# ADC.net
KiCad netlist of a schematic drawn in Altium Designer
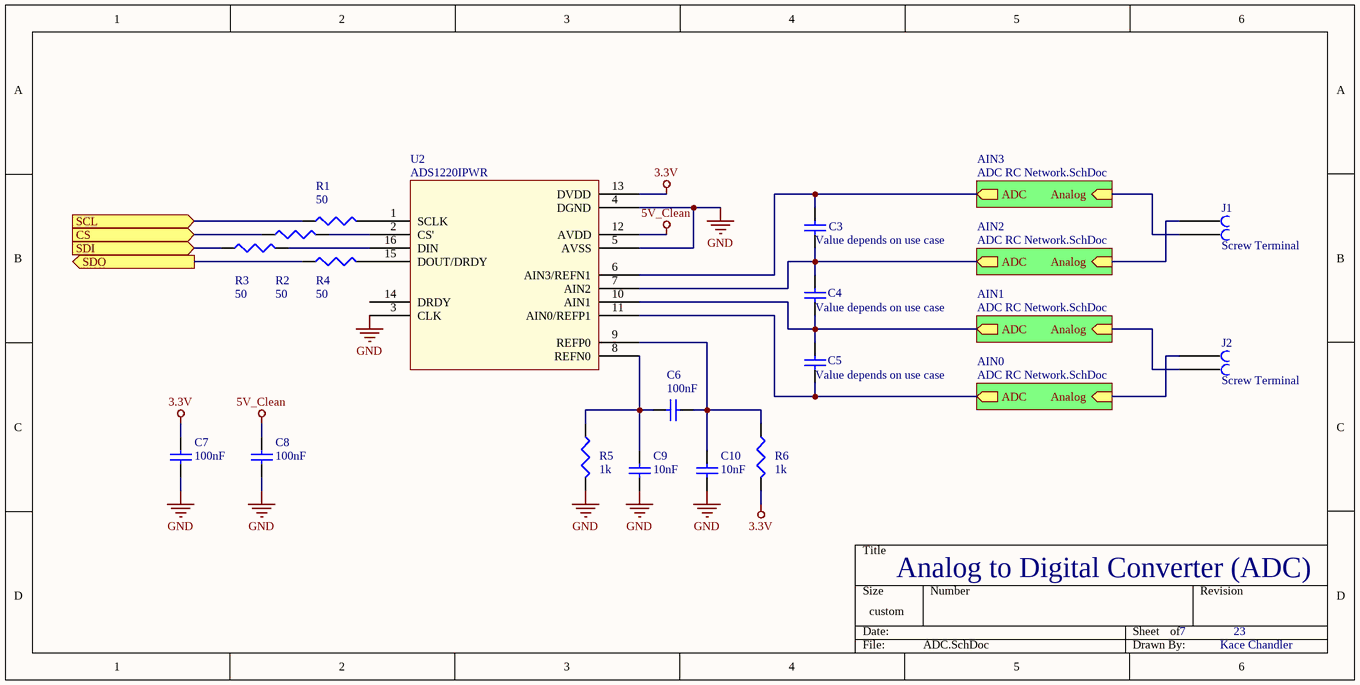
[diagram p0: ADC.SchDoc]

(export (version "E")
  (design (tool "Eeschema 10.0.6"))
  (components
    (comp (ref "C3")
      (value "Value depends on use case")
      (footprint "0603 to 0805 SMD")
      (description "Capacitor")
      (fields (field (name "Comment") "Cap") (field (name "PUBLISHER") "Altium Limited"))
      (libsource (lib "Miscellaneous Devices") (part "Cap"))
    )
    (comp (ref "C4")
      (value "Value depends on use case")
      (footprint "0603 to 0805 SMD")
      (description "Capacitor")
      (fields (field (name "Comment") "Cap") (field (name "PUBLISHER") "Altium Limited"))
      (libsource (lib "Miscellaneous Devices") (part "Cap"))
    )
    (comp (ref "C5")
      (value "Value depends on use case")
      (footprint "0603 to 0805 SMD")
      (description "Capacitor")
      (fields (field (name "Comment") "Cap") (field (name "PUBLISHER") "Altium Limited"))
      (libsource (lib "Miscellaneous Devices") (part "Cap"))
    )
    (comp (ref "C6")
      (value "100nF")
      (footprint "0603 to 0805 SMD")
      (fields (field (name "Comment") "Cap"))
      (libsource (lib "RC0805FR-0751K1L") (part "Cap"))
    )
    (comp (ref "C7")
      (value "100nF")
      (footprint "0603 Footprint")
      (fields (field (name "Comment") "Cap"))
      (libsource (lib "RC0805FR-0751K1L") (part "Cap"))
    )
    (comp (ref "C8")
      (value "100nF")
      (footprint "0603 Footprint")
      (fields (field (name "Comment") "Cap"))
      (libsource (lib "RC0805FR-0751K1L") (part "Cap"))
    )
    (comp (ref "C9")
      (value "10nF")
      (footprint "0603 to 0805 SMD")
      (fields (field (name "Comment") "Cap"))
      (libsource (lib "RC0805FR-0751K1L") (part "Cap"))
    )
    (comp (ref "C10")
      (value "10nF")
      (footprint "0603 to 0805 SMD")
      (fields (field (name "Comment") "Cap"))
      (libsource (lib "RC0805FR-0751K1L") (part "Cap"))
    )
    (comp (ref "J1")
      (value "Screw Terminal")
      (footprint "Screw Terminal")
      (libsource (lib "AvionicsParts") (part "Screw Terminal"))
    )
    (comp (ref "J2")
      (value "Screw Terminal")
      (footprint "Screw Terminal")
      (libsource (lib "AvionicsParts") (part "Screw Terminal"))
    )
    (comp (ref "R1")
      (value "50")
      (description "Resistor")
      (fields (field (name "Comment") "Res3") (field (name "PUBLISHER") "Altium Limited"))
      (libsource (lib "Miscellaneous Devices") (part "Res3"))
    )
    (comp (ref "R2")
      (value "50")
      (description "Resistor")
      (fields (field (name "Comment") "Res3") (field (name "PUBLISHER") "Altium Limited"))
      (libsource (lib "Miscellaneous Devices") (part "Res3"))
    )
    (comp (ref "R3")
      (value "50")
      (description "Resistor")
      (fields (field (name "Comment") "Res3") (field (name "PUBLISHER") "Altium Limited"))
      (libsource (lib "Miscellaneous Devices") (part "Res3"))
    )
    (comp (ref "R4")
      (value "50")
      (description "Resistor")
      (fields (field (name "Comment") "Res3") (field (name "PUBLISHER") "Altium Limited"))
      (libsource (lib "Miscellaneous Devices") (part "Res3"))
    )
    (comp (ref "R5")
      (value "1k")
      (description "Resistor")
      (fields (field (name "Comment") "Res3") (field (name "PUBLISHER") "Altium Limited"))
      (libsource (lib "Miscellaneous Devices") (part "Res3"))
    )
    (comp (ref "R6")
      (value "1k")
      (description "Resistor")
      (fields (field (name "Comment") "Res3") (field (name "PUBLISHER") "Altium Limited"))
      (libsource (lib "Miscellaneous Devices") (part "Res3"))
    )
    (comp (ref "U2")
      (value "Analog to Digital Converter")
      (footprint "SOP65P640X120-16N")
      (description "SOP65P640X120-16N")
      (fields (field (name "MP") "ADS1220IPWR"))
      (libsource (lib "AvionicsParts") (part "Analog to Digital Converter"))
    )
  )
  (nets
    (net (code "1") (name "/ADC") (class "Default")
      (node (ref "C5") (pin "1") (pinfunction "1_1") (pintype "passive"))
      (node (ref "U2") (pin "11") (pinfunction "AIN0/REFP1_11") (pintype "passive"))
    )
    (net (code "2") (name "/ADC_1") (class "Default")
      (node (ref "C3") (pin "2") (pinfunction "2_2") (pintype "passive"))
      (node (ref "U2") (pin "6") (pinfunction "AIN3/REFN1_6") (pintype "passive"))
    )
    (net (code "3") (name "/ADC_2") (class "Default")
      (node (ref "C3") (pin "1") (pinfunction "1_1") (pintype "passive"))
      (node (ref "C4") (pin "1") (pinfunction "1_1") (pintype "passive"))
      (node (ref "U2") (pin "7") (pinfunction "AIN2_7") (pintype "passive"))
    )
    (net (code "4") (name "/ADC_3") (class "Default")
      (node (ref "C4") (pin "2") (pinfunction "2_2") (pintype "passive"))
      (node (ref "C5") (pin "2") (pinfunction "2_2") (pintype "passive"))
      (node (ref "U2") (pin "10") (pinfunction "AIN1_10") (pintype "passive"))
    )
    (net (code "5") (name "/Analog") (class "Default")
      (node (ref "J2") (pin "1") (pinfunction "1_1") (pintype "passive"))
    )
    (net (code "6") (name "/Analog_1") (class "Default")
      (node (ref "J1") (pin "2") (pinfunction "2_2") (pintype "passive"))
    )
    (net (code "7") (name "/Analog_2") (class "Default")
      (node (ref "J1") (pin "1") (pinfunction "1_1") (pintype "passive"))
    )
    (net (code "8") (name "/Analog_3") (class "Default")
      (node (ref "J2") (pin "2") (pinfunction "2_2") (pintype "passive"))
    )
    (net (code "9") (name "/CS") (class "Default")
      (node (ref "R2") (pin "1") (pinfunction "1_1") (pintype "passive"))
    )
    (net (code "10") (name "/SCL") (class "Default")
      (node (ref "R1") (pin "1") (pinfunction "1_1") (pintype "passive"))
    )
    (net (code "11") (name "/SDI") (class "Default")
      (node (ref "R3") (pin "1") (pinfunction "1_1") (pintype "passive"))
    )
    (net (code "12") (name "/SDO") (class "Default")
      (node (ref "R4") (pin "1") (pinfunction "1_1") (pintype "passive"))
    )
    (net (code "13") (name "3.3V") (class "Default")
      (node (ref "C7") (pin "2") (pinfunction "2_2") (pintype "passive"))
      (node (ref "R6") (pin "2") (pinfunction "2_2") (pintype "passive"))
      (node (ref "U2") (pin "13") (pinfunction "DVDD_13") (pintype "passive"))
    )
    (net (code "14") (name "5V_Clean") (class "Default")
      (node (ref "C8") (pin "2") (pinfunction "2_2") (pintype "passive"))
      (node (ref "U2") (pin "12") (pinfunction "AVDD_12") (pintype "passive"))
    )
    (net (code "15") (name "GND") (class "Default")
      (node (ref "C10") (pin "1") (pinfunction "1_1") (pintype "passive"))
      (node (ref "C7") (pin "1") (pinfunction "1_1") (pintype "passive"))
      (node (ref "C8") (pin "1") (pinfunction "1_1") (pintype "passive"))
      (node (ref "C9") (pin "1") (pinfunction "1_1") (pintype "passive"))
      (node (ref "R5") (pin "2") (pinfunction "2_2") (pintype "passive"))
      (node (ref "U2") (pin "3") (pinfunction "CLK_3") (pintype "passive"))
      (node (ref "U2") (pin "4") (pinfunction "DGND_4") (pintype "passive"))
      (node (ref "U2") (pin "5") (pinfunction "AVSS_5") (pintype "passive"))
    )
    (net (code "16") (name "Net-(U2-CS')") (class "Default")
      (node (ref "R2") (pin "2") (pinfunction "2_2") (pintype "passive"))
      (node (ref "U2") (pin "2") (pinfunction "CS'_2") (pintype "passive"))
    )
    (net (code "17") (name "Net-(U2-DIN)") (class "Default")
      (node (ref "R3") (pin "2") (pinfunction "2_2") (pintype "passive"))
      (node (ref "U2") (pin "16") (pinfunction "DIN_16") (pintype "passive"))
    )
    (net (code "18") (name "Net-(U2-DOUT{slash}DRDY)") (class "Default")
      (node (ref "R4") (pin "2") (pinfunction "2_2") (pintype "passive"))
      (node (ref "U2") (pin "15") (pinfunction "DOUT/DRDY_15") (pintype "passive"))
    )
    (net (code "19") (name "Net-(U2-REFN0)") (class "Default")
      (node (ref "C6") (pin "1") (pinfunction "1_1") (pintype "passive"))
      (node (ref "C9") (pin "2") (pinfunction "2_2") (pintype "passive"))
      (node (ref "R5") (pin "1") (pinfunction "1_1") (pintype "passive"))
      (node (ref "U2") (pin "8") (pinfunction "REFN0_8") (pintype "passive"))
    )
    (net (code "20") (name "Net-(U2-REFP0)") (class "Default")
      (node (ref "C10") (pin "2") (pinfunction "2_2") (pintype "passive"))
      (node (ref "C6") (pin "2") (pinfunction "2_2") (pintype "passive"))
      (node (ref "R6") (pin "1") (pinfunction "1_1") (pintype "passive"))
      (node (ref "U2") (pin "9") (pinfunction "REFP0_9") (pintype "passive"))
    )
    (net (code "21") (name "Net-(U2-SCLK)") (class "Default")
      (node (ref "R1") (pin "2") (pinfunction "2_2") (pintype "passive"))
      (node (ref "U2") (pin "1") (pinfunction "SCLK_1") (pintype "passive"))
    )
    (net (code "22") (name "unconnected-(U2-DRDY-Pad14)") (class "Default")
      (node (ref "U2") (pin "14") (pinfunction "DRDY_14") (pintype "passive"))
    )
  )
)
